# 03-POWER.net
KiCad netlist of a schematic drawn in Altium Designer
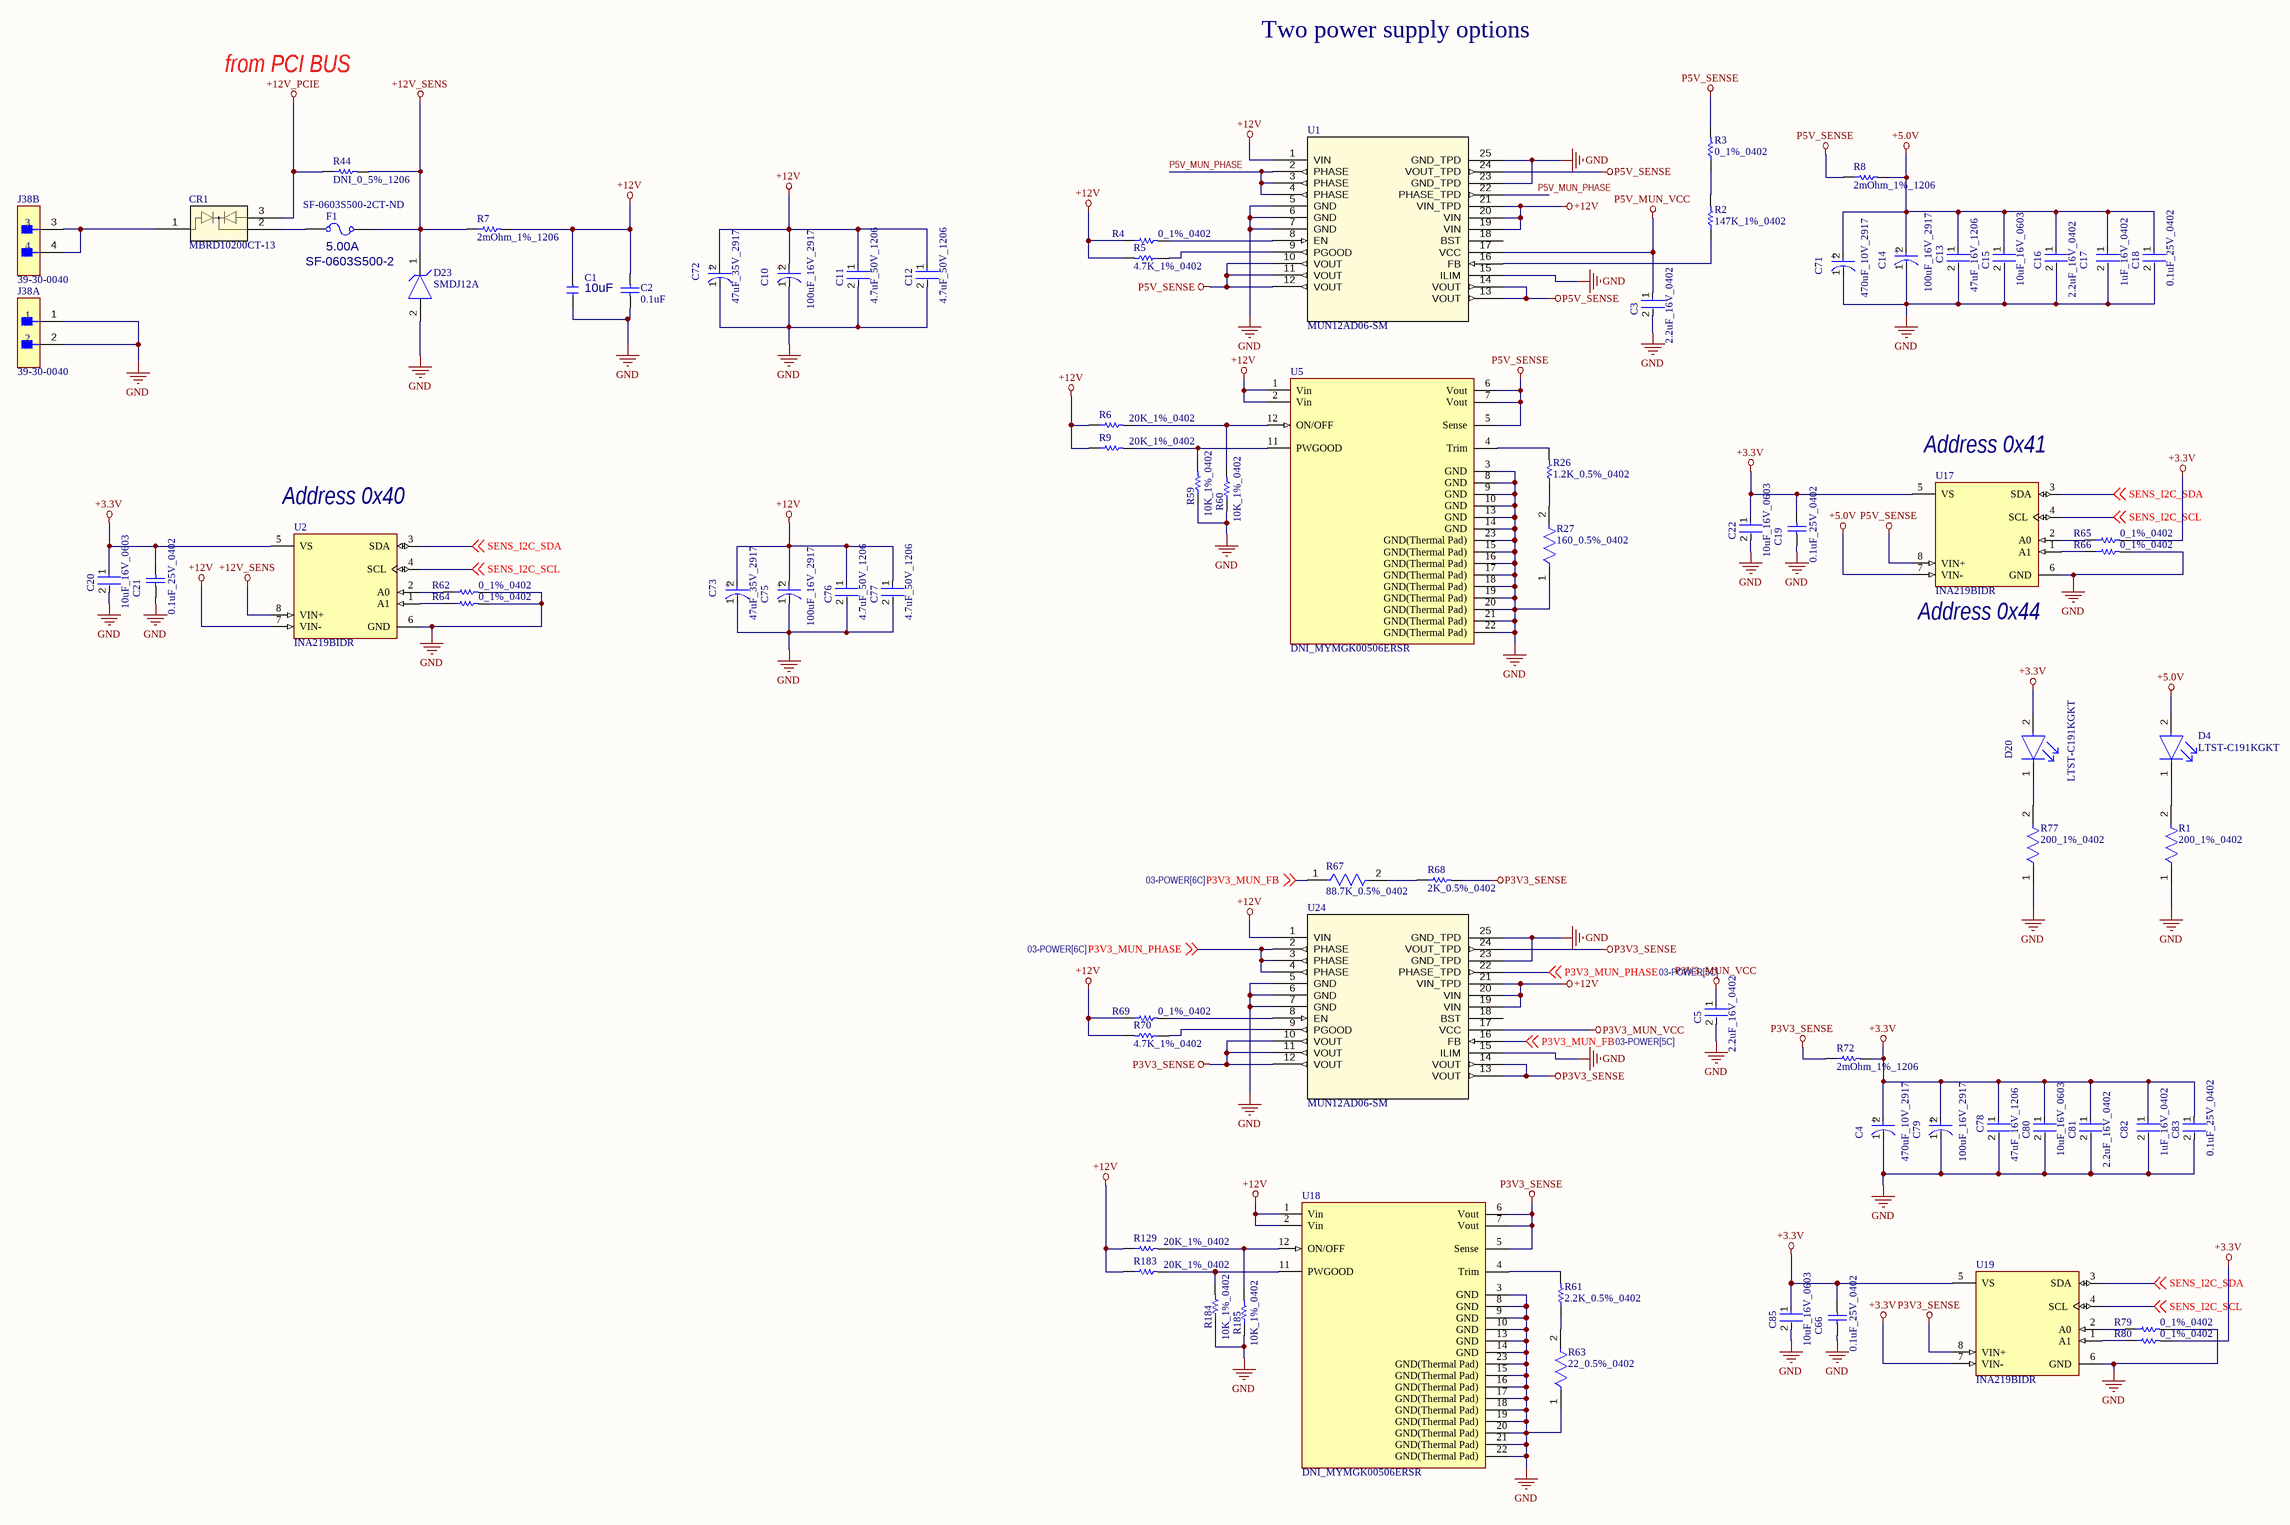
[diagram p0: 03-POWER.SchDoc]

(export (version "E")
  (design (tool "Eeschema 10.0.6"))
  (components
    (comp (ref "C1")
      (value "10uF")
      (footprint "CAPC2012X14N")
      (description "CAP, CER, 10.UF, 25V, 10%, X5R, 0805")
      (fields
        (field (name "MFG PART NUM") "TMK212BBJ106KG-T")
        (field (name "VALENTIUM PART NUM") "<VALENTIUM>")
      )
      (libsource (lib "Capacitors") (part "CAP_0805_10UF_25V"))
    )
    (comp (ref "C2")
      (value "0.1uF")
      (footprint "CAPC1608X87X45ML20T05")
      (description "C0603X104K5RACAUTO")
      (fields (field (name "MANUFACTURER") "Kemet"))
      (libsource (lib "Altium Content Vault") (part "CAP"))
    )
    (comp (ref "C3")
      (value "2.2uF_16V_0402")
      (footprint "FP-C1005-050-0_05-IPC_A")
      (description "Multilayer Ceramic Capacitors 2.2μF ±10% 16V X5R SMD 0402")
      (fields (field (name "TOLERANCE") "10%"))
      (libsource (lib "Altium Content Vault") (part "b4654b650e69147ec39a6b967a45e02"))
    )
    (comp (ref "C4")
      (value "470uF_10V_2917")
      (footprint "FP-TAJE-MFG")
      (description "470uF 10V  ±10% 500mΩ 2917  SMD Tantalum Capacitor")
      (fields (field (name "TOLERANCE") "10%") (field (name "VOLTAGE") "10V"))
      (libsource (lib "Altium Content Vault") (part "203bc49f2ac43e59fd269a8c329ed05"))
    )
    (comp (ref "C5")
      (value "2.2uF_16V_0402")
      (footprint "FP-C1005-050-0_05-IPC_A")
      (description "Multilayer Ceramic Capacitors 2.2μF ±10% 16V X5R SMD 0402")
      (fields (field (name "TOLERANCE") "10%"))
      (libsource (lib "Altium Content Vault") (part "b4654b650e69147ec39a6b967a45e02"))
    )
    (comp (ref "C10")
      (value "100uF_16V_2917")
      (footprint "FP-T495D107K016ATE125-MFG")
      (description "CAP TANT 100UF 10% 16V 2917")
      (fields (field (name "VOLTAGE") "16V") (field (name "TOLERANCE") "10%"))
      (libsource (lib "Altium Content Vault") (part "a00bbbee19879c290e62620ae7e47b1"))
    )
    (comp (ref "C11")
      (value "4.7uF_50V_1206")
      (footprint "FP-GRM31C-0_2-e0_3_0_8-IPC_C")
      (description "Chip Multilayer Ceramic Capacitors for General Purpose, 1206, 4.7uF, X7R, 15%, 10%, 50V")
      (fields (field (name "VOLTAGE") "50V") (field (name "TOLERANCE") "10%"))
      (libsource (lib "Altium Content Vault") (part "02cd4be3c70576c341d710602a673aa"))
    )
    (comp (ref "C12")
      (value "4.7uF_50V_1206")
      (footprint "FP-GRM31C-0_2-e0_3_0_8-IPC_C")
      (description "Chip Multilayer Ceramic Capacitors for General Purpose, 1206, 4.7uF, X7R, 15%, 10%, 50V")
      (fields (field (name "VOLTAGE") "50V") (field (name "TOLERANCE") "10%"))
      (libsource (lib "Altium Content Vault") (part "02cd4be3c70576c341d710602a673aa"))
    )
    (comp (ref "C13")
      (value "47uF_16V_1206")
      (footprint "FP-C3216-160-0_2-MFG")
      (description "Multilayer Ceramic Capacitors 47uF ±20% 16V X5R SMD 1206")
      (fields (field (name "TOLERANCE") "20%"))
      (libsource (lib "Altium Content Vault") (part "11868f565c42a9108669ba33697ecf6"))
    )
    (comp (ref "C14")
      (value "100uF_16V_2917")
      (footprint "FP-T495D107K016ATE125-MFG")
      (description "CAP TANT 100UF 10% 16V 2917")
      (fields (field (name "VOLTAGE") "16V") (field (name "TOLERANCE") "10%"))
      (libsource (lib "Altium Content Vault") (part "a00bbbee19879c290e62620ae7e47b1"))
    )
    (comp (ref "C15")
      (value "10uF_16V_0603")
      (footprint "FP-0603-L_1_6_0_2-W_0_8_0-MFG")
      (description "Multilayer Ceramic Capacitor 10uF 16V X5R 20% SMD 0603 T/R")
      (fields (field (name "TOLERANCE") "20%"))
      (libsource (lib "Altium Content Vault") (part "b4654b650e69147ec39a6b967a45e02"))
    )
    (comp (ref "C16")
      (value "2.2uF_16V_0402")
      (footprint "FP-C1005-050-0_05-IPC_A")
      (description "Multilayer Ceramic Capacitors 2.2μF ±10% 16V X5R SMD 0402")
      (fields (field (name "TOLERANCE") "10%"))
      (libsource (lib "Altium Content Vault") (part "b4654b650e69147ec39a6b967a45e02"))
    )
    (comp (ref "C17")
      (value "1uF_16V_0402")
      (footprint "FP-0402-L_1_0_0_05-W_0_5-IPC_A")
      (description "None")
      (fields (field (name "TOLERANCE") "10%"))
      (libsource (lib "Altium Content Vault") (part "b4654b650e69147ec39a6b967a45e02"))
    )
    (comp (ref "C18")
      (value "0.1uF_25V_0402")
      (footprint "FP-0402-L_1_0_1-W_0_5_0_1-IPC_C")
      (description "General Purpose Ceramic Capacitor, 0402, 100nF, 10%, X7R, 15%, 25V")
      (fields (field (name "VOLTAGE") "25V") (field (name "TOLERANCE") "10%"))
      (libsource (lib "Altium Content Vault") (part "b4654b650e69147ec39a6b967a45e02"))
    )
    (comp (ref "C19")
      (value "0.1uF_25V_0402")
      (footprint "CAPC1005X56X25NL10T15")
      (fields
        (field (name "PART NUMBER") "04023D104KAT2A")
        (field (name "MANUFACTURER") "AVX Interconnect / Elco")
      )
      (libsource (lib "Altium Content Vault") (part "CAP"))
    )
    (comp (ref "C20")
      (value "10uF_16V_0603")
      (footprint "FP-0603-L_1_6_0_2-W_0_8_0-MFG")
      (description "Multilayer Ceramic Capacitor 10uF 16V X5R 20% SMD 0603 T/R")
      (fields (field (name "TOLERANCE") "20%"))
      (libsource (lib "Altium Content Vault") (part "b4654b650e69147ec39a6b967a45e02"))
    )
    (comp (ref "C21")
      (value "0.1uF_25V_0402")
      (footprint "CAPC1005X56X25NL10T15")
      (fields
        (field (name "PART NUMBER") "04023D104KAT2A")
        (field (name "MANUFACTURER") "AVX Interconnect / Elco")
      )
      (libsource (lib "Altium Content Vault") (part "CAP"))
    )
    (comp (ref "C22")
      (value "10uF_16V_0603")
      (footprint "FP-0603-L_1_6_0_2-W_0_8_0-MFG")
      (description "Multilayer Ceramic Capacitor 10uF 16V X5R 20% SMD 0603 T/R")
      (fields (field (name "TOLERANCE") "20%"))
      (libsource (lib "Altium Content Vault") (part "b4654b650e69147ec39a6b967a45e02"))
    )
    (comp (ref "C66")
      (value "0.1uF_25V_0402")
      (footprint "CAPC1005X56X25NL10T15")
      (fields
        (field (name "PART NUMBER") "04023D104KAT2A")
        (field (name "MANUFACTURER") "AVX Interconnect / Elco")
      )
      (libsource (lib "Altium Content Vault") (part "CAP"))
    )
    (comp (ref "C71")
      (value "470uF_10V_2917")
      (footprint "FP-TAJE-MFG")
      (description "470uF 10V  ±10% 500mΩ 2917  SMD Tantalum Capacitor")
      (fields (field (name "TOLERANCE") "10%") (field (name "VOLTAGE") "10V"))
      (libsource (lib "Altium Content Vault") (part "203bc49f2ac43e59fd269a8c329ed05"))
    )
    (comp (ref "C72")
      (value "47uF_35V_2917")
      (footprint "FP-T521X476M035ATE030-MFG")
      (description "CAP TANT POLY 47UF 35V 2917")
      (fields (field (name "TOLERANCE") "20%"))
      (libsource (lib "Altium Content Vault") (part "a00bbbee19879c290e62620ae7e47b1"))
    )
    (comp (ref "C73")
      (value "47uF_35V_2917")
      (footprint "FP-T521X476M035ATE030-MFG")
      (description "CAP TANT POLY 47UF 35V 2917")
      (fields (field (name "TOLERANCE") "20%"))
      (libsource (lib "Altium Content Vault") (part "a00bbbee19879c290e62620ae7e47b1"))
    )
    (comp (ref "C75")
      (value "100uF_16V_2917")
      (footprint "FP-T495D107K016ATE125-MFG")
      (description "CAP TANT 100UF 10% 16V 2917")
      (fields (field (name "VOLTAGE") "16V") (field (name "TOLERANCE") "10%"))
      (libsource (lib "Altium Content Vault") (part "a00bbbee19879c290e62620ae7e47b1"))
    )
    (comp (ref "C76")
      (value "4.7uF_50V_1206")
      (footprint "FP-GRM31C-0_2-e0_3_0_8-IPC_C")
      (description "Chip Multilayer Ceramic Capacitors for General Purpose, 1206, 4.7uF, X7R, 15%, 10%, 50V")
      (fields (field (name "VOLTAGE") "50V") (field (name "TOLERANCE") "10%"))
      (libsource (lib "Altium Content Vault") (part "02cd4be3c70576c341d710602a673aa"))
    )
    (comp (ref "C77")
      (value "4.7uF_50V_1206")
      (footprint "FP-GRM31C-0_2-e0_3_0_8-IPC_C")
      (description "Chip Multilayer Ceramic Capacitors for General Purpose, 1206, 4.7uF, X7R, 15%, 10%, 50V")
      (fields (field (name "VOLTAGE") "50V") (field (name "TOLERANCE") "10%"))
      (libsource (lib "Altium Content Vault") (part "02cd4be3c70576c341d710602a673aa"))
    )
    (comp (ref "C78")
      (value "47uF_16V_1206")
      (footprint "FP-C3216-160-0_2-MFG")
      (description "Multilayer Ceramic Capacitors 47uF ±20% 16V X5R SMD 1206")
      (fields (field (name "TOLERANCE") "20%"))
      (libsource (lib "Altium Content Vault") (part "11868f565c42a9108669ba33697ecf6"))
    )
    (comp (ref "C79")
      (value "100uF_16V_2917")
      (footprint "FP-T495D107K016ATE125-MFG")
      (description "CAP TANT 100UF 10% 16V 2917")
      (fields (field (name "VOLTAGE") "16V") (field (name "TOLERANCE") "10%"))
      (libsource (lib "Altium Content Vault") (part "a00bbbee19879c290e62620ae7e47b1"))
    )
    (comp (ref "C80")
      (value "10uF_16V_0603")
      (footprint "FP-0603-L_1_6_0_2-W_0_8_0-MFG")
      (description "Multilayer Ceramic Capacitor 10uF 16V X5R 20% SMD 0603 T/R")
      (fields (field (name "TOLERANCE") "20%"))
      (libsource (lib "Altium Content Vault") (part "b4654b650e69147ec39a6b967a45e02"))
    )
    (comp (ref "C81")
      (value "2.2uF_16V_0402")
      (footprint "FP-C1005-050-0_05-IPC_A")
      (description "Multilayer Ceramic Capacitors 2.2μF ±10% 16V X5R SMD 0402")
      (fields (field (name "TOLERANCE") "10%"))
      (libsource (lib "Altium Content Vault") (part "b4654b650e69147ec39a6b967a45e02"))
    )
    (comp (ref "C82")
      (value "1uF_16V_0402")
      (footprint "FP-0402-L_1_0_0_05-W_0_5-IPC_A")
      (description "None")
      (fields (field (name "TOLERANCE") "10%"))
      (libsource (lib "Altium Content Vault") (part "b4654b650e69147ec39a6b967a45e02"))
    )
    (comp (ref "C83")
      (value "0.1uF_25V_0402")
      (footprint "FP-0402-L_1_0_1-W_0_5_0_1-IPC_C")
      (description "General Purpose Ceramic Capacitor, 0402, 100nF, 10%, X7R, 15%, 25V")
      (fields (field (name "VOLTAGE") "25V") (field (name "TOLERANCE") "10%"))
      (libsource (lib "Altium Content Vault") (part "b4654b650e69147ec39a6b967a45e02"))
    )
    (comp (ref "C85")
      (value "10uF_16V_0603")
      (footprint "FP-0603-L_1_6_0_2-W_0_8_0-MFG")
      (description "Multilayer Ceramic Capacitor 10uF 16V X5R 20% SMD 0603 T/R")
      (fields (field (name "TOLERANCE") "20%"))
      (libsource (lib "Altium Content Vault") (part "b4654b650e69147ec39a6b967a45e02"))
    )
    (comp (ref "CR1")
      (value "MBRD10200CT-13")
      (footprint "TO252(DPAK)_DIO")
      (description "No Description Available")
      (libsource (lib "MBRD10200CT-13") (part "MBRD10200CT-13"))
    )
    (comp (ref "D4")
      (value "LTST-C191KGKT")
      (footprint "FP-LTST-C191KGKT-MFG")
      (description "LED GREEN CLEAR SMD")
      (libsource (lib "Altium Content Vault") (part "8706943c75ba83719d021d2fdc84c58"))
    )
    (comp (ref "D20")
      (value "LTST-C191KGKT")
      (footprint "FP-LTST-C191KGKT-MFG")
      (description "LED GREEN CLEAR SMD")
      (libsource (lib "Altium Content Vault") (part "8706943c75ba83719d021d2fdc84c58"))
    )
    (comp (ref "D23")
      (value "SMDJ12A")
      (footprint "FP-DO-214AB_SMC_J-Bend-MFG")
      (description "TVS DIODE 12V 19.9V DO214AB")
      (libsource (lib "Altium Content Vault") (part "673ecd2ea4d7fb87b4005b0cb348b7d"))
    )
    (comp (ref "F1")
      (value "5.00A")
      (footprint "FUSM1608X60N")
      (description "FUSE SLOW 5.00A 32V M 0603")
      (fields
        (field (name "MFG PART NUM") "SF-0603S500-2")
        (field (name "VALENTIUM PART NUM") "<VALENTIUM>")
        (field (name "SUPPLIER PART NUMBER 1") "SF-0603S500-2CT-ND")
        (field (name "Comment") "FUSE_0603_5.00A")
      )
      (libsource (lib "Passives") (part "FUSE_0603_2.00A"))
    )
    (comp (ref "J38")
      (value "39-30-0040")
      (footprint "FP-39-30-0040-MFG")
      (description "CONN HEADER R/A 4POS 4.2MM")
      (fields
        (field (name "OCTOPART") "https://octopart.com/39-30-0040-molex-277428")
        (field (name "MANUFACTURER") "Molex")
      )
      (libsource (lib "Altium Content Vault") (part "ac72c5313ea981db199dbd0e8237b04"))
    )
    (comp (ref "R1")
      (value "200_1%_0402")
      (footprint "FP-ERJ2RK-IPC_A")
      (description "RES SMD 200 OHM 1% 1/10W 0402")
      (fields (field (name "TOLERANCE") "1%"))
      (libsource (lib "Altium Content Vault") (part "1029c3af85768c4190bb7ad29bc67b5"))
    )
    (comp (ref "R2")
      (value "147K_1%_0402")
      (footprint "RESC1005X40X25ML05T10")
      (fields (field (name "MANUFACTURER") "Yageo / Phycomp") (field (name "PART NUMBER") "RC0402FR-07147KL"))
      (libsource (lib "Altium Content Vault") (part "RES"))
    )
    (comp (ref "R3")
      (value "0_1%_0402")
      (footprint "RESC1005X40X25LL05T05")
      (description "Chip Resistor, 0 Ohm, 0.1 W, -55 to 155 degC, 0402 (1005 Metric), RoHS, Tape and Reel")
      (fields (field (name "MANUFACTURER") "Panasonic") (field (name "TOLERANCE") "5%"))
      (libsource (lib "Altium Content Vault") (part "RES-2"))
    )
    (comp (ref "R4")
      (value "0_1%_0402")
      (footprint "RESC1005X40X25LL05T05")
      (description "Chip Resistor, 0 Ohm, 0.1 W, -55 to 155 degC, 0402 (1005 Metric), RoHS, Tape and Reel")
      (fields (field (name "MANUFACTURER") "Panasonic") (field (name "TOLERANCE") "5%"))
      (libsource (lib "Altium Content Vault") (part "RES-2"))
    )
    (comp (ref "R5")
      (value "4.7K_1%_0402")
      (footprint "RESC1005X40X25NL10T10")
      (fields (field (name "MANUFACTURER") "Bourns") (field (name "PART NUMBER") "CR0402-FX-4701GLF"))
      (libsource (lib "Altium Content Vault") (part "RES"))
    )
    (comp (ref "R6")
      (value "20K_1%_0402")
      (footprint "RESC1005X40X25NL10T10")
      (fields (field (name "PART NUMBER") "MC00625W0402120K") (field (name "MANUFACTURER") "Multicomp"))
      (libsource (lib "Altium Content Vault") (part "RES"))
    )
    (comp (ref "R7")
      (value "2mOhm_1%_1206")
      (footprint "RESC3216X89X64NL25T25")
      (fields (field (name "MANUFACTURER") "Vishay Dale") (field (name "PART NUMBER") "WSL12062L000FEA18"))
      (libsource (lib "Altium Content Vault") (part "RES"))
    )
    (comp (ref "R8")
      (value "2mOhm_1%_1206")
      (footprint "RESC3216X89X64NL25T25")
      (fields (field (name "MANUFACTURER") "Vishay Dale") (field (name "PART NUMBER") "WSL12062L000FEA18"))
      (libsource (lib "Altium Content Vault") (part "RES"))
    )
    (comp (ref "R9")
      (value "20K_1%_0402")
      (footprint "RESC1005X40X25NL10T10")
      (fields (field (name "PART NUMBER") "MC00625W0402120K") (field (name "MANUFACTURER") "Multicomp"))
      (libsource (lib "Altium Content Vault") (part "RES"))
    )
    (comp (ref "R26")
      (value "1.2K_0.5%_0402")
      (footprint "RESC1005X40X25ML10T10")
      (fields (field (name "PART NUMBER") "ERA-2AED122X") (field (name "MANUFACTURER") "Panasonic"))
      (libsource (lib "Altium Content Vault") (part "RES"))
    )
    (comp (ref "R27")
      (value "160_0.5%_0402")
      (footprint "FP-RT0402-MFG")
      (description "RES SMD 160 OHM 0.5% 1/16W 0402")
      (fields
        (field (name "TOLERANCE") "0.005")
        (field (name "OCTOPART") "https://octopart.com/rt0402dre07160rl-yageo-1216058")
      )
      (libsource (lib "Altium Content Vault") (part "1029c3af85768c4190bb7ad29bc67b5"))
    )
    (comp (ref "R44")
      (value "DNI_0_5%_1206")
      (footprint "RESC3116X65X50ML20T20")
      (fields (field (name "PART NUMBER") "CRCW12060000Z0EAHP") (field (name "MANUFACTURER") "Vishay Dale"))
      (libsource (lib "Altium Content Vault") (part "RES"))
    )
    (comp (ref "R59")
      (value "10K_1%_0402")
      (footprint "RESC1005X40X25NL10T10")
      (fields (field (name "MANUFACTURER") "Bourns") (field (name "PART NUMBER") "CR0402-FX-1002GLF"))
      (libsource (lib "Altium Content Vault") (part "RES"))
    )
    (comp (ref "R60")
      (value "10K_1%_0402")
      (footprint "RESC1005X40X25NL10T10")
      (fields (field (name "MANUFACTURER") "Bourns") (field (name "PART NUMBER") "CR0402-FX-1002GLF"))
      (libsource (lib "Altium Content Vault") (part "RES"))
    )
    (comp (ref "R61")
      (value "2.2K_0.5%_0402")
      (footprint "RESC1005X40X25ML10T10")
      (fields (field (name "PART NUMBER") "ERA-2AED222X") (field (name "MANUFACTURER") "Panasonic"))
      (libsource (lib "Altium Content Vault") (part "RES"))
    )
    (comp (ref "R62")
      (value "0_1%_0402")
      (footprint "RESC1005X40X25LL05T05")
      (description "Chip Resistor, 0 Ohm, 0.1 W, -55 to 155 degC, 0402 (1005 Metric), RoHS, Tape and Reel")
      (fields (field (name "MANUFACTURER") "Panasonic") (field (name "TOLERANCE") "5%"))
      (libsource (lib "Altium Content Vault") (part "RES-2"))
    )
    (comp (ref "R63")
      (value "22_0.5%_0402")
      (footprint "FP-RG1005-IPC_A")
      (description "Automotive Metal Thin Film Chip Resistor, 0402, 22Ω, 0.5%, 100ppm/°C, 0.0625W, 75V")
      (fields (field (name "TOLERANCE") "0.5%"))
      (libsource (lib "Altium Content Vault") (part "1029c3af85768c4190bb7ad29bc67b5"))
    )
    (comp (ref "R64")
      (value "0_1%_0402")
      (footprint "RESC1005X40X25LL05T05")
      (description "Chip Resistor, 0 Ohm, 0.1 W, -55 to 155 degC, 0402 (1005 Metric), RoHS, Tape and Reel")
      (fields (field (name "MANUFACTURER") "Panasonic") (field (name "TOLERANCE") "5%"))
      (libsource (lib "Altium Content Vault") (part "RES-2"))
    )
    (comp (ref "R65")
      (value "0_1%_0402")
      (footprint "RESC1005X40X25LL05T05")
      (description "Chip Resistor, 0 Ohm, 0.1 W, -55 to 155 degC, 0402 (1005 Metric), RoHS, Tape and Reel")
      (fields (field (name "MANUFACTURER") "Panasonic") (field (name "TOLERANCE") "5%"))
      (libsource (lib "Altium Content Vault") (part "RES-2"))
    )
    (comp (ref "R66")
      (value "0_1%_0402")
      (footprint "RESC1005X40X25LL05T05")
      (description "Chip Resistor, 0 Ohm, 0.1 W, -55 to 155 degC, 0402 (1005 Metric), RoHS, Tape and Reel")
      (fields (field (name "MANUFACTURER") "Panasonic") (field (name "TOLERANCE") "5%"))
      (libsource (lib "Altium Content Vault") (part "RES-2"))
    )
    (comp (ref "R67")
      (value "88.7K_0.5%_0402")
      (footprint "FP-RT0402-MFG")
      (description "RES SMD 88.7K OHM 0.5% 1/16W")
      (fields
        (field (name "OCTOPART") "https://octopart.com/rt0402dre0788k7l-yageo-1439224")
        (field (name "MANUFACTURER") "Yageo")
      )
      (libsource (lib "Altium Content Vault") (part "1029c3af85768c4190bb7ad29bc67b5"))
    )
    (comp (ref "R68")
      (value "2K_0.5%_0402")
      (footprint "RESC1005X35X25LL10T10")
      (fields (field (name "PART NUMBER") "RT0402DRD072KL") (field (name "MANUFACTURER") "Yageo"))
      (libsource (lib "Altium Content Vault") (part "RES"))
    )
    (comp (ref "R69")
      (value "0_1%_0402")
      (footprint "RESC1005X40X25LL05T05")
      (description "Chip Resistor, 0 Ohm, 0.1 W, -55 to 155 degC, 0402 (1005 Metric), RoHS, Tape and Reel")
      (fields (field (name "MANUFACTURER") "Panasonic") (field (name "TOLERANCE") "5%"))
      (libsource (lib "Altium Content Vault") (part "RES-2"))
    )
    (comp (ref "R70")
      (value "4.7K_1%_0402")
      (footprint "RESC1005X40X25NL10T10")
      (fields (field (name "MANUFACTURER") "Bourns") (field (name "PART NUMBER") "CR0402-FX-4701GLF"))
      (libsource (lib "Altium Content Vault") (part "RES"))
    )
    (comp (ref "R72")
      (value "2mOhm_1%_1206")
      (footprint "RESC3216X89X64NL25T25")
      (fields (field (name "MANUFACTURER") "Vishay Dale") (field (name "PART NUMBER") "WSL12062L000FEA18"))
      (libsource (lib "Altium Content Vault") (part "RES"))
    )
    (comp (ref "R77")
      (value "200_1%_0402")
      (footprint "FP-ERJ2RK-IPC_A")
      (description "RES SMD 200 OHM 1% 1/10W 0402")
      (fields (field (name "TOLERANCE") "1%"))
      (libsource (lib "Altium Content Vault") (part "1029c3af85768c4190bb7ad29bc67b5"))
    )
    (comp (ref "R79")
      (value "0_1%_0402")
      (footprint "RESC1005X40X25LL05T05")
      (description "Chip Resistor, 0 Ohm, 0.1 W, -55 to 155 degC, 0402 (1005 Metric), RoHS, Tape and Reel")
      (fields (field (name "MANUFACTURER") "Panasonic") (field (name "TOLERANCE") "5%"))
      (libsource (lib "Altium Content Vault") (part "RES-2"))
    )
    (comp (ref "R80")
      (value "0_1%_0402")
      (footprint "RESC1005X40X25LL05T05")
      (description "Chip Resistor, 0 Ohm, 0.1 W, -55 to 155 degC, 0402 (1005 Metric), RoHS, Tape and Reel")
      (fields (field (name "MANUFACTURER") "Panasonic") (field (name "TOLERANCE") "5%"))
      (libsource (lib "Altium Content Vault") (part "RES-2"))
    )
    (comp (ref "R129")
      (value "20K_1%_0402")
      (footprint "RESC1005X40X25NL10T10")
      (fields (field (name "PART NUMBER") "MC00625W0402120K") (field (name "MANUFACTURER") "Multicomp"))
      (libsource (lib "Altium Content Vault") (part "RES"))
    )
    (comp (ref "R183")
      (value "20K_1%_0402")
      (footprint "RESC1005X40X25NL10T10")
      (fields (field (name "PART NUMBER") "MC00625W0402120K") (field (name "MANUFACTURER") "Multicomp"))
      (libsource (lib "Altium Content Vault") (part "RES"))
    )
    (comp (ref "R184")
      (value "10K_1%_0402")
      (footprint "RESC1005X40X25NL10T10")
      (fields (field (name "MANUFACTURER") "Bourns") (field (name "PART NUMBER") "CR0402-FX-1002GLF"))
      (libsource (lib "Altium Content Vault") (part "RES"))
    )
    (comp (ref "R185")
      (value "10K_1%_0402")
      (footprint "RESC1005X40X25NL10T10")
      (fields (field (name "MANUFACTURER") "Bourns") (field (name "PART NUMBER") "CR0402-FX-1002GLF"))
      (libsource (lib "Altium Content Vault") (part "RES"))
    )
    (comp (ref "U1")
      (value "MUN12AD06-SM")
      (footprint "MUN12AD06-SM_CYN")
      (description "No Description Available")
      (libsource (lib "MUN12AD06-SM") (part "MUN12AD06-SM"))
    )
    (comp (ref "U2")
      (value "INA219BIDR")
      (footprint "FP-D0008A-MFG")
      (description "IC MONITOR PWR/CURR BIDIR 8-SOIC")
      (libsource (lib "Altium Content Vault") (part "41cc1aee4cbc9fa2660a15773fa0e79"))
    )
    (comp (ref "U5")
      (value "DNI_MYMGK00506ERSR")
      (footprint "FP-MYMGK-12-MFG")
      (description "DC DC CONVERTER 0.7-5V")
      (libsource (lib "Altium Content Vault") (part "57b8017c1ce60d7b1362a625e7a4ba1"))
    )
    (comp (ref "U17")
      (value "INA219BIDR")
      (footprint "FP-D0008A-MFG")
      (description "IC MONITOR PWR/CURR BIDIR 8-SOIC")
      (libsource (lib "Altium Content Vault") (part "41cc1aee4cbc9fa2660a15773fa0e79"))
    )
    (comp (ref "U18")
      (value "DNI_MYMGK00506ERSR")
      (footprint "FP-MYMGK-12-MFG")
      (description "DC DC CONVERTER 0.7-5V")
      (libsource (lib "Altium Content Vault") (part "57b8017c1ce60d7b1362a625e7a4ba1"))
    )
    (comp (ref "U19")
      (value "INA219BIDR")
      (footprint "FP-D0008A-MFG")
      (description "IC MONITOR PWR/CURR BIDIR 8-SOIC")
      (libsource (lib "Altium Content Vault") (part "41cc1aee4cbc9fa2660a15773fa0e79"))
    )
    (comp (ref "U24")
      (value "MUN12AD06-SM")
      (footprint "MUN12AD06-SM_CYN")
      (description "No Description Available")
      (libsource (lib "MUN12AD06-SM") (part "MUN12AD06-SM"))
    )
  )
  (nets
    (net (code "1") (name "+3.3V") (class "Default")
      (node (ref "C19") (pin "2") (pinfunction "2_2") (pintype "passive"))
      (node (ref "C20") (pin "1") (pinfunction "1_1") (pintype "passive"))
      (node (ref "C21") (pin "2") (pinfunction "2_2") (pintype "passive"))
      (node (ref "C22") (pin "1") (pinfunction "1_1") (pintype "passive"))
      (node (ref "C4") (pin "2") (pinfunction "A_2") (pintype "passive"))
      (node (ref "C66") (pin "2") (pinfunction "2_2") (pintype "passive"))
      (node (ref "C78") (pin "1") (pinfunction "1_1") (pintype "passive"))
      (node (ref "C79") (pin "2") (pinfunction "A_2") (pintype "passive"))
      (node (ref "C80") (pin "1") (pinfunction "1_1") (pintype "passive"))
      (node (ref "C81") (pin "1") (pinfunction "1_1") (pintype "passive"))
      (node (ref "C82") (pin "1") (pinfunction "1_1") (pintype "passive"))
      (node (ref "C83") (pin "1") (pinfunction "1_1") (pintype "passive"))
      (node (ref "C85") (pin "1") (pinfunction "1_1") (pintype "passive"))
      (node (ref "D20") (pin "2") (pinfunction "A_2") (pintype "passive"))
      (node (ref "R65") (pin "2") (pinfunction "2_2") (pintype "passive"))
      (node (ref "R72") (pin "2") (pinfunction "2_2") (pintype "passive"))
      (node (ref "R80") (pin "2") (pinfunction "2_2") (pintype "passive"))
      (node (ref "U17") (pin "5") (pinfunction "VS_5") (pintype "power_in"))
      (node (ref "U19") (pin "5") (pinfunction "VS_5") (pintype "power_in"))
      (node (ref "U19") (pin "7") (pinfunction "VIN-_7") (pintype "input"))
      (node (ref "U2") (pin "5") (pinfunction "VS_5") (pintype "power_in"))
    )
    (net (code "2") (name "+5.0V") (class "Default")
      (node (ref "C13") (pin "1") (pinfunction "1_1") (pintype "passive"))
      (node (ref "C14") (pin "2") (pinfunction "A_2") (pintype "passive"))
      (node (ref "C15") (pin "1") (pinfunction "1_1") (pintype "passive"))
      (node (ref "C16") (pin "1") (pinfunction "1_1") (pintype "passive"))
      (node (ref "C17") (pin "1") (pinfunction "1_1") (pintype "passive"))
      (node (ref "C18") (pin "1") (pinfunction "1_1") (pintype "passive"))
      (node (ref "C71") (pin "2") (pinfunction "A_2") (pintype "passive"))
      (node (ref "D4") (pin "2") (pinfunction "A_2") (pintype "passive"))
      (node (ref "R8") (pin "2") (pinfunction "2_2") (pintype "passive"))
      (node (ref "U17") (pin "7") (pinfunction "VIN-_7") (pintype "input"))
    )
    (net (code "3") (name "+12V") (class "Default")
      (node (ref "C1") (pin "1") (pinfunction "1_1") (pintype "passive"))
      (node (ref "C10") (pin "2") (pinfunction "A_2") (pintype "passive"))
      (node (ref "C11") (pin "1") (pinfunction "1_1") (pintype "passive"))
      (node (ref "C12") (pin "1") (pinfunction "1_1") (pintype "passive"))
      (node (ref "C2") (pin "2") (pinfunction "2_2") (pintype "passive"))
      (node (ref "C72") (pin "2") (pinfunction "A_2") (pintype "passive"))
      (node (ref "C73") (pin "2") (pinfunction "A_2") (pintype "passive"))
      (node (ref "C75") (pin "2") (pinfunction "A_2") (pintype "passive"))
      (node (ref "C76") (pin "1") (pinfunction "1_1") (pintype "passive"))
      (node (ref "C77") (pin "1") (pinfunction "1_1") (pintype "passive"))
      (node (ref "R129") (pin "1") (pinfunction "1_1") (pintype "passive"))
      (node (ref "R183") (pin "1") (pinfunction "1_1") (pintype "passive"))
      (node (ref "R4") (pin "1") (pinfunction "1_1") (pintype "passive"))
      (node (ref "R5") (pin "2") (pinfunction "2_2") (pintype "passive"))
      (node (ref "R6") (pin "1") (pinfunction "1_1") (pintype "passive"))
      (node (ref "R69") (pin "1") (pinfunction "1_1") (pintype "passive"))
      (node (ref "R7") (pin "2") (pinfunction "2_2") (pintype "passive"))
      (node (ref "R70") (pin "2") (pinfunction "2_2") (pintype "passive"))
      (node (ref "R9") (pin "1") (pinfunction "1_1") (pintype "passive"))
      (node (ref "U1") (pin "1") (pinfunction "VIN_1") (pintype "power_in"))
      (node (ref "U1") (pin "19") (pinfunction "VIN_19") (pintype "power_in"))
      (node (ref "U1") (pin "20") (pinfunction "VIN_20") (pintype "power_in"))
      (node (ref "U1") (pin "21") (pinfunction "VIN_TPD_21") (pintype "power_in"))
      (node (ref "U18") (pin "1") (pinfunction "Vin_1") (pintype "power_in"))
      (node (ref "U18") (pin "2") (pinfunction "Vin_2") (pintype "power_in"))
      (node (ref "U2") (pin "7") (pinfunction "VIN-_7") (pintype "input"))
      (node (ref "U24") (pin "1") (pinfunction "VIN_1") (pintype "power_in"))
      (node (ref "U24") (pin "19") (pinfunction "VIN_19") (pintype "power_in"))
      (node (ref "U24") (pin "20") (pinfunction "VIN_20") (pintype "power_in"))
      (node (ref "U24") (pin "21") (pinfunction "VIN_TPD_21") (pintype "power_in"))
      (node (ref "U5") (pin "1") (pinfunction "Vin_1") (pintype "power_in"))
      (node (ref "U5") (pin "2") (pinfunction "Vin_2") (pintype "power_in"))
    )
    (net (code "4") (name "+12V_PCIE") (class "Default")
      (node (ref "CR1") (pin "3") (pinfunction "3_3") (pintype "passive"))
      (node (ref "R44") (pin "1") (pinfunction "1_1") (pintype "passive"))
    )
    (net (code "5") (name "+12V_SENS") (class "Default")
      (node (ref "D23") (pin "1") (pinfunction "C_1") (pintype "passive"))
      (node (ref "F1") (pin "2") (pinfunction "2_2") (pintype "passive"))
      (node (ref "R44") (pin "2") (pinfunction "2_2") (pintype "passive"))
      (node (ref "R7") (pin "1") (pinfunction "1_1") (pintype "passive"))
      (node (ref "U2") (pin "8") (pinfunction "VIN+_8") (pintype "input"))
    )
    (net (code "6") (name "/P5V_MUN_PHASE") (class "Default")
      (node (ref "U1") (pin "2") (pinfunction "PHASE_2") (pintype "output"))
      (node (ref "U1") (pin "22") (pinfunction "PHASE_TPD_22") (pintype "output"))
      (node (ref "U1") (pin "3") (pinfunction "PHASE_3") (pintype "output"))
      (node (ref "U1") (pin "4") (pinfunction "PHASE_4") (pintype "output"))
    )
    (net (code "7") (name "GND") (class "Default")
      (node (ref "C1") (pin "2") (pinfunction "2_2") (pintype "passive"))
      (node (ref "C10") (pin "1") (pinfunction "C_1") (pintype "passive"))
      (node (ref "C11") (pin "2") (pinfunction "2_2") (pintype "passive"))
      (node (ref "C12") (pin "2") (pinfunction "2_2") (pintype "passive"))
      (node (ref "C13") (pin "2") (pinfunction "2_2") (pintype "passive"))
      (node (ref "C14") (pin "1") (pinfunction "C_1") (pintype "passive"))
      (node (ref "C15") (pin "2") (pinfunction "2_2") (pintype "passive"))
      (node (ref "C16") (pin "2") (pinfunction "2_2") (pintype "passive"))
      (node (ref "C17") (pin "2") (pinfunction "2_2") (pintype "passive"))
      (node (ref "C18") (pin "2") (pinfunction "2_2") (pintype "passive"))
      (node (ref "C19") (pin "1") (pinfunction "1_1") (pintype "passive"))
      (node (ref "C2") (pin "1") (pinfunction "1_1") (pintype "passive"))
      (node (ref "C20") (pin "2") (pinfunction "2_2") (pintype "passive"))
      (node (ref "C21") (pin "1") (pinfunction "1_1") (pintype "passive"))
      (node (ref "C22") (pin "2") (pinfunction "2_2") (pintype "passive"))
      (node (ref "C3") (pin "2") (pinfunction "2_2") (pintype "passive"))
      (node (ref "C4") (pin "1") (pinfunction "C_1") (pintype "passive"))
      (node (ref "C5") (pin "2") (pinfunction "2_2") (pintype "passive"))
      (node (ref "C66") (pin "1") (pinfunction "1_1") (pintype "passive"))
      (node (ref "C71") (pin "1") (pinfunction "C_1") (pintype "passive"))
      (node (ref "C72") (pin "1") (pinfunction "C_1") (pintype "passive"))
      (node (ref "C73") (pin "1") (pinfunction "C_1") (pintype "passive"))
      (node (ref "C75") (pin "1") (pinfunction "C_1") (pintype "passive"))
      (node (ref "C76") (pin "2") (pinfunction "2_2") (pintype "passive"))
      (node (ref "C77") (pin "2") (pinfunction "2_2") (pintype "passive"))
      (node (ref "C78") (pin "2") (pinfunction "2_2") (pintype "passive"))
      (node (ref "C79") (pin "1") (pinfunction "C_1") (pintype "passive"))
      (node (ref "C80") (pin "2") (pinfunction "2_2") (pintype "passive"))
      (node (ref "C81") (pin "2") (pinfunction "2_2") (pintype "passive"))
      (node (ref "C82") (pin "2") (pinfunction "2_2") (pintype "passive"))
      (node (ref "C83") (pin "2") (pinfunction "2_2") (pintype "passive"))
      (node (ref "C85") (pin "2") (pinfunction "2_2") (pintype "passive"))
      (node (ref "D23") (pin "2") (pinfunction "A_2") (pintype "passive"))
      (node (ref "J38") (pin "1") (pinfunction "1_1") (pintype "passive"))
      (node (ref "J38") (pin "2") (pinfunction "2_2") (pintype "passive"))
      (node (ref "R1") (pin "1") (pinfunction "1_1") (pintype "passive"))
      (node (ref "R184") (pin "1") (pinfunction "1_1") (pintype "passive"))
      (node (ref "R185") (pin "1") (pinfunction "1_1") (pintype "passive"))
      (node (ref "R27") (pin "1") (pinfunction "1_1") (pintype "passive"))
      (node (ref "R59") (pin "1") (pinfunction "1_1") (pintype "passive"))
      (node (ref "R60") (pin "1") (pinfunction "1_1") (pintype "passive"))
      (node (ref "R62") (pin "2") (pinfunction "2_2") (pintype "passive"))
      (node (ref "R63") (pin "1") (pinfunction "1_1") (pintype "passive"))
      (node (ref "R64") (pin "2") (pinfunction "2_2") (pintype "passive"))
      (node (ref "R66") (pin "2") (pinfunction "2_2") (pintype "passive"))
      (node (ref "R77") (pin "1") (pinfunction "1_1") (pintype "passive"))
      (node (ref "R79") (pin "2") (pinfunction "2_2") (pintype "passive"))
      (node (ref "U1") (pin "15") (pinfunction "ILIM_15") (pintype "passive"))
      (node (ref "U1") (pin "23") (pinfunction "GND_TPD_23") (pintype "power_in"))
      (node (ref "U1") (pin "25") (pinfunction "GND_TPD_25") (pintype "power_in"))
      (node (ref "U1") (pin "5") (pinfunction "GND_5") (pintype "power_in"))
      (node (ref "U1") (pin "6") (pinfunction "GND_6") (pintype "power_in"))
      (node (ref "U1") (pin "7") (pinfunction "GND_7") (pintype "power_in"))
      (node (ref "U17") (pin "6") (pinfunction "GND_6") (pintype "power_in"))
      (node (ref "U18") (pin "10") (pinfunction "GND_10") (pintype "power_in"))
      (node (ref "U18") (pin "13") (pinfunction "GND_13") (pintype "power_in"))
      (node (ref "U18") (pin "14") (pinfunction "GND_14") (pintype "power_in"))
      (node (ref "U18") (pin "15") (pinfunction "GND(Thermal_Pad)_15") (pintype "power_in"))
      (node (ref "U18") (pin "16") (pinfunction "GND(Thermal_Pad)_16") (pintype "power_in"))
      (node (ref "U18") (pin "17") (pinfunction "GND(Thermal_Pad)_17") (pintype "power_in"))
      (node (ref "U18") (pin "18") (pinfunction "GND(Thermal_Pad)_18") (pintype "power_in"))
      (node (ref "U18") (pin "19") (pinfunction "GND(Thermal_Pad)_19") (pintype "power_in"))
      (node (ref "U18") (pin "20") (pinfunction "GND(Thermal_Pad)_20") (pintype "power_in"))
      (node (ref "U18") (pin "21") (pinfunction "GND(Thermal_Pad)_21") (pintype "power_in"))
      (node (ref "U18") (pin "22") (pinfunction "GND(Thermal_Pad)_22") (pintype "power_in"))
      (node (ref "U18") (pin "23") (pinfunction "GND(Thermal_Pad)_23") (pintype "power_in"))
      (node (ref "U18") (pin "3") (pinfunction "GND_3") (pintype "power_in"))
      (node (ref "U18") (pin "8") (pinfunction "GND_8") (pintype "power_in"))
      (node (ref "U18") (pin "9") (pinfunction "GND_9") (pintype "power_in"))
      (node (ref "U19") (pin "6") (pinfunction "GND_6") (pintype "power_in"))
      (node (ref "U2") (pin "6") (pinfunction "GND_6") (pintype "power_in"))
      (node (ref "U24") (pin "15") (pinfunction "ILIM_15") (pintype "passive"))
      (node (ref "U24") (pin "23") (pinfunction "GND_TPD_23") (pintype "power_in"))
      (node (ref "U24") (pin "25") (pinfunction "GND_TPD_25") (pintype "power_in"))
      (node (ref "U24") (pin "5") (pinfunction "GND_5") (pintype "power_in"))
      (node (ref "U24") (pin "6") (pinfunction "GND_6") (pintype "power_in"))
      (node (ref "U24") (pin "7") (pinfunction "GND_7") (pintype "power_in"))
      (node (ref "U5") (pin "10") (pinfunction "GND_10") (pintype "power_in"))
      (node (ref "U5") (pin "13") (pinfunction "GND_13") (pintype "power_in"))
      (node (ref "U5") (pin "14") (pinfunction "GND_14") (pintype "power_in"))
      (node (ref "U5") (pin "15") (pinfunction "GND(Thermal_Pad)_15") (pintype "power_in"))
      (node (ref "U5") (pin "16") (pinfunction "GND(Thermal_Pad)_16") (pintype "power_in"))
      (node (ref "U5") (pin "17") (pinfunction "GND(Thermal_Pad)_17") (pintype "power_in"))
      (node (ref "U5") (pin "18") (pinfunction "GND(Thermal_Pad)_18") (pintype "power_in"))
      (node (ref "U5") (pin "19") (pinfunction "GND(Thermal_Pad)_19") (pintype "power_in"))
      (node (ref "U5") (pin "20") (pinfunction "GND(Thermal_Pad)_20") (pintype "power_in"))
      (node (ref "U5") (pin "21") (pinfunction "GND(Thermal_Pad)_21") (pintype "power_in"))
      (node (ref "U5") (pin "22") (pinfunction "GND(Thermal_Pad)_22") (pintype "power_in"))
      (node (ref "U5") (pin "23") (pinfunction "GND(Thermal_Pad)_23") (pintype "power_in"))
      (node (ref "U5") (pin "3") (pinfunction "GND_3") (pintype "power_in"))
      (node (ref "U5") (pin "8") (pinfunction "GND_8") (pintype "power_in"))
      (node (ref "U5") (pin "9") (pinfunction "GND_9") (pintype "power_in"))
    )
    (net (code "8") (name "Net-(CR1-Pad1)") (class "Default")
      (node (ref "CR1") (pin "1") (pinfunction "1_1") (pintype "passive"))
      (node (ref "J38") (pin "3") (pinfunction "3_3") (pintype "passive"))
      (node (ref "J38") (pin "4") (pinfunction "4_4") (pintype "passive"))
    )
    (net (code "9") (name "Net-(CR1-Pad2)") (class "Default")
      (node (ref "CR1") (pin "2") (pinfunction "2_2") (pintype "passive"))
      (node (ref "F1") (pin "1") (pinfunction "1_1") (pintype "passive"))
    )
    (net (code "10") (name "Net-(D4-C)") (class "Default")
      (node (ref "D4") (pin "1") (pinfunction "C_1") (pintype "passive"))
      (node (ref "R1") (pin "2") (pinfunction "2_2") (pintype "passive"))
    )
    (net (code "11") (name "Net-(D20-C)") (class "Default")
      (node (ref "D20") (pin "1") (pinfunction "C_1") (pintype "passive"))
      (node (ref "R77") (pin "2") (pinfunction "2_2") (pintype "passive"))
    )
    (net (code "12") (name "Net-(R2-Pad2)") (class "Default")
      (node (ref "R2") (pin "2") (pinfunction "2_2") (pintype "passive"))
      (node (ref "R3") (pin "1") (pinfunction "1_1") (pintype "passive"))
    )
    (net (code "13") (name "Net-(R26-Pad1)") (class "Default")
      (node (ref "R26") (pin "1") (pinfunction "1_1") (pintype "passive"))
      (node (ref "R27") (pin "2") (pinfunction "2_2") (pintype "passive"))
    )
    (net (code "14") (name "Net-(R61-Pad1)") (class "Default")
      (node (ref "R61") (pin "1") (pinfunction "1_1") (pintype "passive"))
      (node (ref "R63") (pin "2") (pinfunction "2_2") (pintype "passive"))
    )
    (net (code "15") (name "Net-(R67-Pad2)") (class "Default")
      (node (ref "R67") (pin "2") (pinfunction "2_2") (pintype "passive"))
      (node (ref "R68") (pin "1") (pinfunction "1_1") (pintype "passive"))
    )
    (net (code "16") (name "Net-(U1-EN)") (class "Default")
      (node (ref "R4") (pin "2") (pinfunction "2_2") (pintype "passive"))
      (node (ref "U1") (pin "8") (pinfunction "EN_8") (pintype "input"))
    )
    (net (code "17") (name "Net-(U1-FB)") (class "Default")
      (node (ref "R2") (pin "1") (pinfunction "1_1") (pintype "passive"))
      (node (ref "U1") (pin "16") (pinfunction "FB_16") (pintype "input"))
    )
    (net (code "18") (name "Net-(U1-PGOOD)") (class "Default")
      (node (ref "R5") (pin "1") (pinfunction "1_1") (pintype "passive"))
      (node (ref "U1") (pin "9") (pinfunction "PGOOD_9") (pintype "output"))
    )
    (net (code "19") (name "Net-(U2-A0)") (class "Default")
      (node (ref "R62") (pin "1") (pinfunction "1_1") (pintype "passive"))
      (node (ref "U2") (pin "2") (pinfunction "A0_2") (pintype "input"))
    )
    (net (code "20") (name "Net-(U2-A1)") (class "Default")
      (node (ref "R64") (pin "1") (pinfunction "1_1") (pintype "passive"))
      (node (ref "U2") (pin "1") (pinfunction "A1_1") (pintype "input"))
    )
    (net (code "21") (name "Net-(U5-ON{slash}OFF)") (class "Default")
      (node (ref "R6") (pin "2") (pinfunction "2_2") (pintype "passive"))
      (node (ref "R60") (pin "2") (pinfunction "2_2") (pintype "passive"))
      (node (ref "U5") (pin "12") (pinfunction "ON/OFF_12") (pintype "input"))
    )
    (net (code "22") (name "Net-(U5-PWGOOD)") (class "Default")
      (node (ref "R59") (pin "2") (pinfunction "2_2") (pintype "passive"))
      (node (ref "R9") (pin "2") (pinfunction "2_2") (pintype "passive"))
      (node (ref "U5") (pin "11") (pinfunction "PWGOOD_11") (pintype "open_collector"))
    )
    (net (code "23") (name "Net-(U5-Trim)") (class "Default")
      (node (ref "R26") (pin "2") (pinfunction "2_2") (pintype "passive"))
      (node (ref "U5") (pin "4") (pinfunction "Trim_4") (pintype "passive"))
    )
    (net (code "24") (name "Net-(U17-A0)") (class "Default")
      (node (ref "R65") (pin "1") (pinfunction "1_1") (pintype "passive"))
      (node (ref "U17") (pin "2") (pinfunction "A0_2") (pintype "input"))
    )
    (net (code "25") (name "Net-(U17-A1)") (class "Default")
      (node (ref "R66") (pin "1") (pinfunction "1_1") (pintype "passive"))
      (node (ref "U17") (pin "1") (pinfunction "A1_1") (pintype "input"))
    )
    (net (code "26") (name "Net-(U18-ON{slash}OFF)") (class "Default")
      (node (ref "R129") (pin "2") (pinfunction "2_2") (pintype "passive"))
      (node (ref "R185") (pin "2") (pinfunction "2_2") (pintype "passive"))
      (node (ref "U18") (pin "12") (pinfunction "ON/OFF_12") (pintype "input"))
    )
    (net (code "27") (name "Net-(U18-PWGOOD)") (class "Default")
      (node (ref "R183") (pin "2") (pinfunction "2_2") (pintype "passive"))
      (node (ref "R184") (pin "2") (pinfunction "2_2") (pintype "passive"))
      (node (ref "U18") (pin "11") (pinfunction "PWGOOD_11") (pintype "open_collector"))
    )
    (net (code "28") (name "Net-(U18-Trim)") (class "Default")
      (node (ref "R61") (pin "2") (pinfunction "2_2") (pintype "passive"))
      (node (ref "U18") (pin "4") (pinfunction "Trim_4") (pintype "passive"))
    )
    (net (code "29") (name "Net-(U19-A0)") (class "Default")
      (node (ref "R79") (pin "1") (pinfunction "1_1") (pintype "passive"))
      (node (ref "U19") (pin "2") (pinfunction "A0_2") (pintype "input"))
    )
    (net (code "30") (name "Net-(U19-A1)") (class "Default")
      (node (ref "R80") (pin "1") (pinfunction "1_1") (pintype "passive"))
      (node (ref "U19") (pin "1") (pinfunction "A1_1") (pintype "input"))
    )
    (net (code "31") (name "Net-(U24-EN)") (class "Default")
      (node (ref "R69") (pin "2") (pinfunction "2_2") (pintype "passive"))
      (node (ref "U24") (pin "8") (pinfunction "EN_8") (pintype "input"))
    )
    (net (code "32") (name "Net-(U24-PGOOD)") (class "Default")
      (node (ref "R70") (pin "1") (pinfunction "1_1") (pintype "passive"))
      (node (ref "U24") (pin "9") (pinfunction "PGOOD_9") (pintype "output"))
    )
    (net (code "33") (name "P3V3_MUN_FB") (class "Default")
      (node (ref "R67") (pin "1") (pinfunction "1_1") (pintype "passive"))
      (node (ref "U24") (pin "16") (pinfunction "FB_16") (pintype "input"))
    )
    (net (code "34") (name "P3V3_MUN_PHASE") (class "Default")
      (node (ref "U24") (pin "2") (pinfunction "PHASE_2") (pintype "output"))
      (node (ref "U24") (pin "22") (pinfunction "PHASE_TPD_22") (pintype "output"))
      (node (ref "U24") (pin "3") (pinfunction "PHASE_3") (pintype "output"))
      (node (ref "U24") (pin "4") (pinfunction "PHASE_4") (pintype "output"))
    )
    (net (code "35") (name "P3V3_MUN_VCC") (class "Default")
      (node (ref "C5") (pin "1") (pinfunction "1_1") (pintype "passive"))
      (node (ref "U24") (pin "17") (pinfunction "VCC_17") (pintype "power_in"))
    )
    (net (code "36") (name "P3V3_SENSE") (class "Default")
      (node (ref "R68") (pin "2") (pinfunction "2_2") (pintype "passive"))
      (node (ref "R72") (pin "1") (pinfunction "1_1") (pintype "passive"))
      (node (ref "U18") (pin "5") (pinfunction "Sense_5") (pintype "passive"))
      (node (ref "U18") (pin "6") (pinfunction "Vout_6") (pintype "power_in"))
      (node (ref "U18") (pin "7") (pinfunction "Vout_7") (pintype "power_in"))
      (node (ref "U19") (pin "8") (pinfunction "VIN+_8") (pintype "input"))
      (node (ref "U24") (pin "10") (pinfunction "VOUT_10") (pintype "output"))
      (node (ref "U24") (pin "11") (pinfunction "VOUT_11") (pintype "output"))
      (node (ref "U24") (pin "12") (pinfunction "VOUT_12") (pintype "output"))
      (node (ref "U24") (pin "13") (pinfunction "VOUT_13") (pintype "output"))
      (node (ref "U24") (pin "14") (pinfunction "VOUT_14") (pintype "output"))
      (node (ref "U24") (pin "24") (pinfunction "VOUT_TPD_24") (pintype "output"))
    )
    (net (code "37") (name "P5V_MUN_VCC") (class "Default")
      (node (ref "C3") (pin "1") (pinfunction "1_1") (pintype "passive"))
      (node (ref "U1") (pin "17") (pinfunction "VCC_17") (pintype "power_in"))
    )
    (net (code "38") (name "P5V_SENSE") (class "Default")
      (node (ref "R3") (pin "2") (pinfunction "2_2") (pintype "passive"))
      (node (ref "R8") (pin "1") (pinfunction "1_1") (pintype "passive"))
      (node (ref "U1") (pin "10") (pinfunction "VOUT_10") (pintype "output"))
      (node (ref "U1") (pin "11") (pinfunction "VOUT_11") (pintype "output"))
      (node (ref "U1") (pin "12") (pinfunction "VOUT_12") (pintype "output"))
      (node (ref "U1") (pin "13") (pinfunction "VOUT_13") (pintype "output"))
      (node (ref "U1") (pin "14") (pinfunction "VOUT_14") (pintype "output"))
      (node (ref "U1") (pin "24") (pinfunction "VOUT_TPD_24") (pintype "output"))
      (node (ref "U17") (pin "8") (pinfunction "VIN+_8") (pintype "input"))
      (node (ref "U5") (pin "5") (pinfunction "Sense_5") (pintype "passive"))
      (node (ref "U5") (pin "6") (pinfunction "Vout_6") (pintype "power_in"))
      (node (ref "U5") (pin "7") (pinfunction "Vout_7") (pintype "power_in"))
    )
    (net (code "39") (name "SENS_I2C_SCL") (class "Default")
      (node (ref "U17") (pin "4") (pinfunction "SCL_4") (pintype "bidirectional"))
      (node (ref "U19") (pin "4") (pinfunction "SCL_4") (pintype "bidirectional"))
      (node (ref "U2") (pin "4") (pinfunction "SCL_4") (pintype "bidirectional"))
    )
    (net (code "40") (name "SENS_I2C_SDA") (class "Default")
      (node (ref "U17") (pin "3") (pinfunction "SDA_3") (pintype "bidirectional"))
      (node (ref "U19") (pin "3") (pinfunction "SDA_3") (pintype "bidirectional"))
      (node (ref "U2") (pin "3") (pinfunction "SDA_3") (pintype "bidirectional"))
    )
    (net (code "41") (name "unconnected-(U1-BST-Pad18)") (class "Default")
      (node (ref "U1") (pin "18") (pinfunction "BST_18") (pintype "power_in"))
    )
    (net (code "42") (name "unconnected-(U24-BST-Pad18)") (class "Default")
      (node (ref "U24") (pin "18") (pinfunction "BST_18") (pintype "power_in"))
    )
  )
)
